# Smarttree_CMU_4.net
KiCad netlist of a schematic drawn in EAGLE
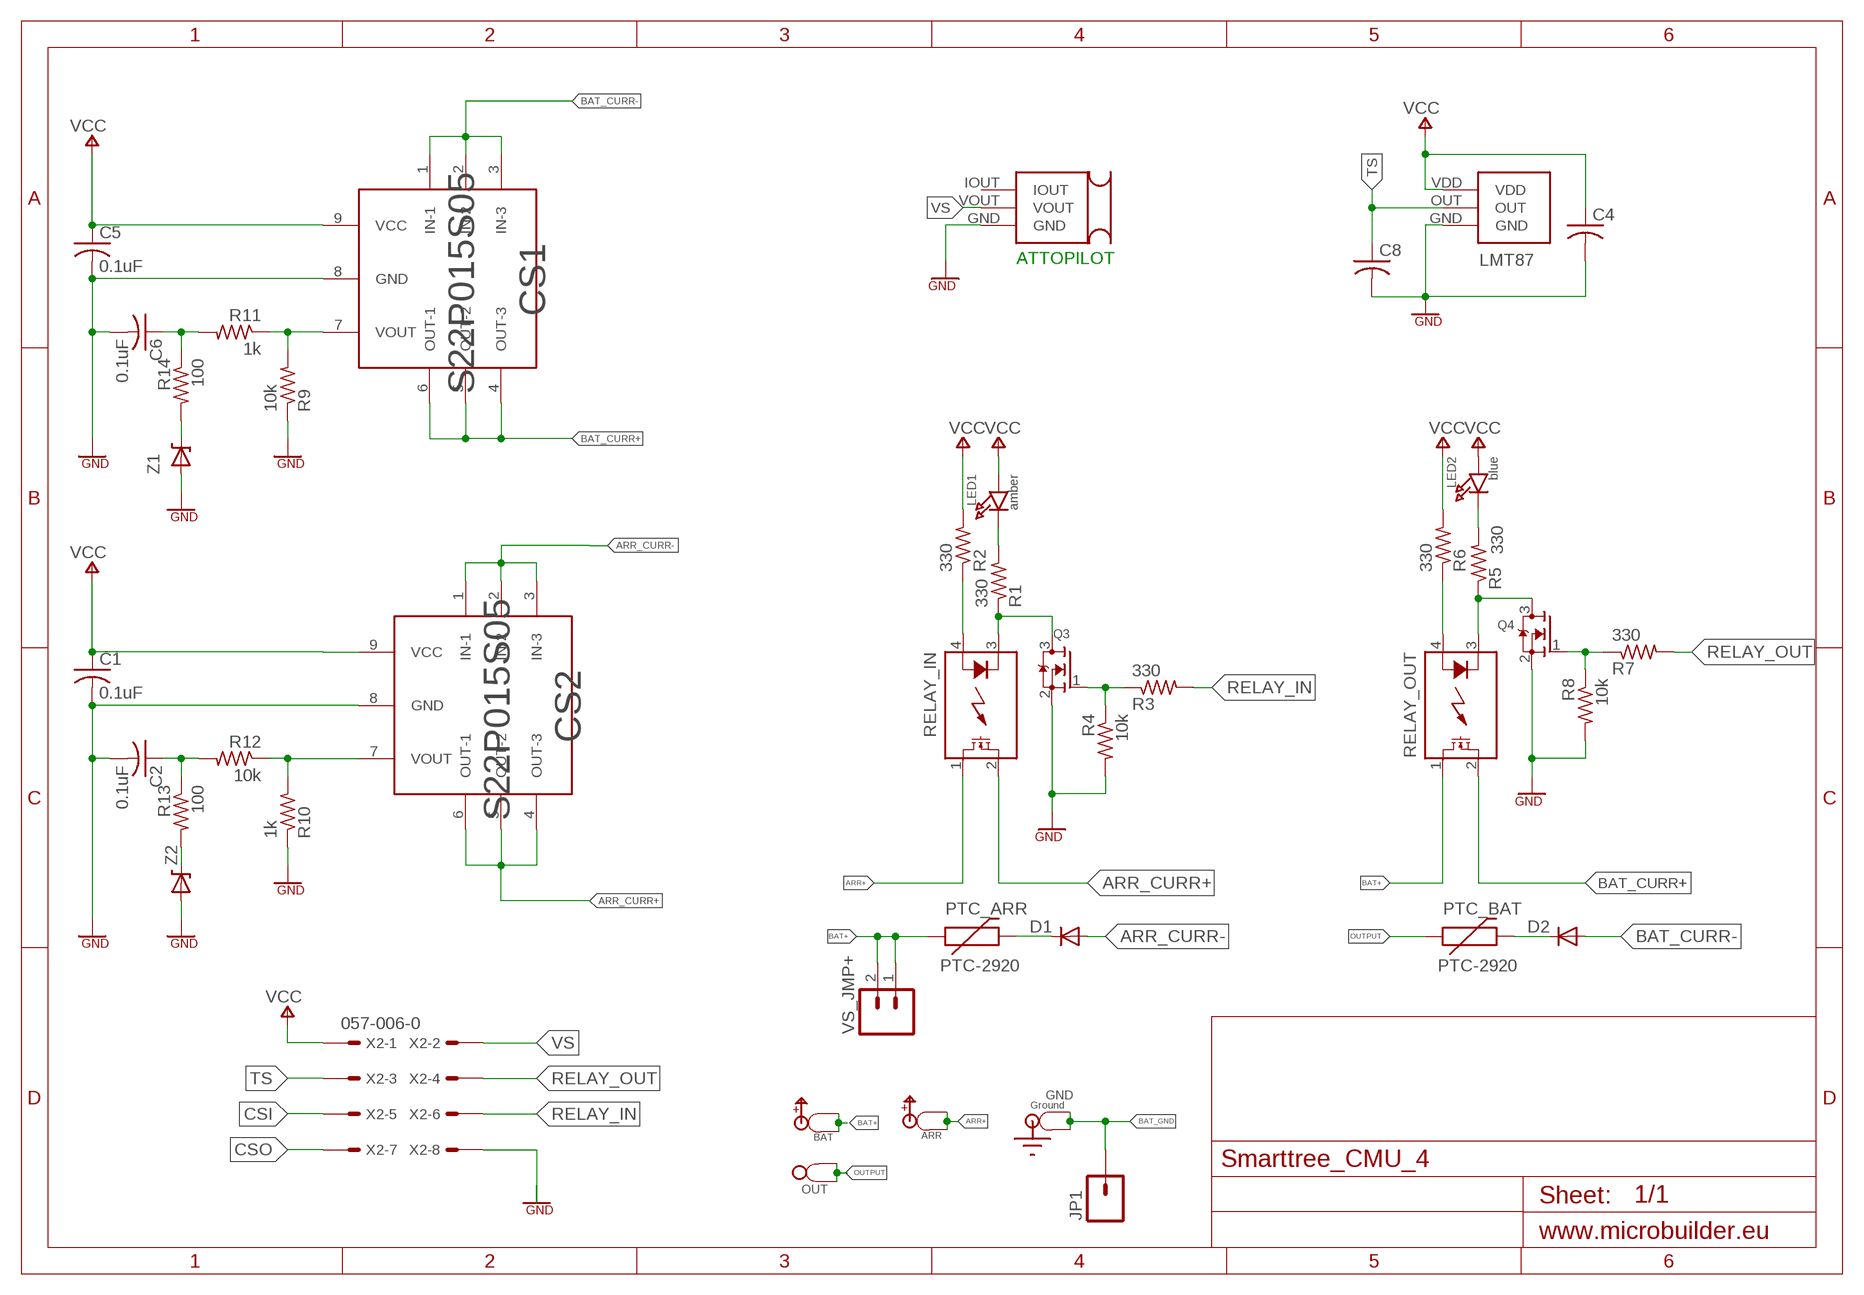
[diagram p0: schematic, sheet 1]

(export (version "E")
  (design (tool "Eeschema 10.0.6"))
  (components
    (comp (ref "ARR")
      (value "SPADE-POWER")
      (footprint "eagle-import:SPADE-POWER")
      (libsource (lib "eagle-import") (part "SPADE-POWER"))
    )
    (comp (ref "ATTOPILOT")
      (value "ATTOPILOT_VOLT")
      (footprint "eagle-import:TH_BKOT")
      (libsource (lib "eagle-import") (part "ATTOPILOT_VOLT"))
    )
    (comp (ref "BAT")
      (value "SPADE-POWER")
      (footprint "eagle-import:SPADE-POWER")
      (libsource (lib "eagle-import") (part "SPADE-POWER"))
    )
    (comp (ref "C1")
      (value "0.1uF")
      (footprint "eagle-import:C0805")
      (libsource (lib "eagle-import") (part "C-USC0805"))
    )
    (comp (ref "C2")
      (value "0.1uF")
      (footprint "eagle-import:C0805")
      (libsource (lib "eagle-import") (part "C-USC0805"))
    )
    (comp (ref "C4")
      (value "C-USC0805")
      (footprint "eagle-import:C0805")
      (libsource (lib "eagle-import") (part "C-USC0805"))
    )
    (comp (ref "C5")
      (value "0.1uF")
      (footprint "eagle-import:C0805")
      (libsource (lib "eagle-import") (part "C-USC0805"))
    )
    (comp (ref "C6")
      (value "0.1uF")
      (footprint "eagle-import:C0805")
      (libsource (lib "eagle-import") (part "C-USC0805"))
    )
    (comp (ref "C8")
      (value "C-USC0805")
      (footprint "eagle-import:C0805")
      (libsource (lib "eagle-import") (part "C-USC0805"))
    )
    (comp (ref "CS1")
      (value "S22P015S05")
      (footprint "eagle-import:S22P015S05")
      (libsource (lib "eagle-import") (part "S22P015S05"))
    )
    (comp (ref "CS2")
      (value "S22P015S05")
      (footprint "eagle-import:S22P015S05")
      (libsource (lib "eagle-import") (part "S22P015S05"))
    )
    (comp (ref "D1")
      (value "DIODE-SOD106-R")
      (footprint "eagle-import:SOD106-R")
      (libsource (lib "eagle-import") (part "DIODE-SOD106-R"))
    )
    (comp (ref "D2")
      (value "DIODE-SOD106-R")
      (footprint "eagle-import:SOD106-R")
      (libsource (lib "eagle-import") (part "DIODE-SOD106-R"))
    )
    (comp (ref "GND")
      (value "SPADE-GROUND")
      (footprint "eagle-import:SPADE-GROUND")
      (libsource (lib "eagle-import") (part "SPADE-GROUND"))
    )
    (comp (ref "JP1")
      (value "M01OFFSET")
      (footprint "eagle-import:1X01_OFFSET")
      (libsource (lib "eagle-import") (part "M01OFFSET"))
    )
    (comp (ref "LED1")
      (value "amber")
      (footprint "eagle-import:CHIPLED_0805")
      (libsource (lib "eagle-import") (part "LED0805"))
    )
    (comp (ref "LED2")
      (value "blue")
      (footprint "eagle-import:CHIPLED_0805")
      (libsource (lib "eagle-import") (part "LED0805"))
    )
    (comp (ref "LMT87")
      (value "LMT87_PAC")
      (footprint "eagle-import:LMT87_TO")
      (libsource (lib "eagle-import") (part "LMT87_PAC"))
    )
    (comp (ref "OUT")
      (value "SPADE-TERMINALPTH")
      (footprint "eagle-import:SPADE-TERMINAL")
      (libsource (lib "eagle-import") (part "SPADE-TERMINALPTH"))
    )
    (comp (ref "PTC_ARR")
      (value "PTC-2920")
      (footprint "eagle-import:PTC-2920")
      (libsource (lib "eagle-import") (part "PTC-2920"))
    )
    (comp (ref "PTC_BAT")
      (value "PTC-2920")
      (footprint "eagle-import:PTC-2920")
      (libsource (lib "eagle-import") (part "PTC-2920"))
    )
    (comp (ref "Q3")
      (value "MOSFET-NREFLOW")
      (footprint "eagle-import:SOT23")
      (libsource (lib "eagle-import") (part "MOSFET-NREFLOW"))
    )
    (comp (ref "Q4")
      (value "MOSFET-NREFLOW")
      (footprint "eagle-import:SOT23")
      (libsource (lib "eagle-import") (part "MOSFET-NREFLOW"))
    )
    (comp (ref "R1")
      (value "330")
      (footprint "eagle-import:R0805")
      (libsource (lib "eagle-import") (part "R-US_R0805"))
    )
    (comp (ref "R2")
      (value "330")
      (footprint "eagle-import:R0805")
      (libsource (lib "eagle-import") (part "R-US_R0805"))
    )
    (comp (ref "R3")
      (value "330")
      (footprint "eagle-import:R0805")
      (libsource (lib "eagle-import") (part "R-US_R0805"))
    )
    (comp (ref "R4")
      (value "10k")
      (footprint "eagle-import:R0805")
      (libsource (lib "eagle-import") (part "R-US_R0805"))
    )
    (comp (ref "R5")
      (value "330")
      (footprint "eagle-import:R0805")
      (libsource (lib "eagle-import") (part "R-US_R0805"))
    )
    (comp (ref "R6")
      (value "330")
      (footprint "eagle-import:R0805")
      (libsource (lib "eagle-import") (part "R-US_R0805"))
    )
    (comp (ref "R7")
      (value "330")
      (footprint "eagle-import:R0805")
      (libsource (lib "eagle-import") (part "R-US_R0805"))
    )
    (comp (ref "R8")
      (value "10k")
      (footprint "eagle-import:R0805")
      (libsource (lib "eagle-import") (part "R-US_R0805"))
    )
    (comp (ref "R9")
      (value "10k")
      (footprint "eagle-import:R0805")
      (libsource (lib "eagle-import") (part "R-US_R0805"))
    )
    (comp (ref "R10")
      (value "1k")
      (footprint "eagle-import:R0805")
      (libsource (lib "eagle-import") (part "R-US_R0805"))
    )
    (comp (ref "R11")
      (value "1k")
      (footprint "eagle-import:R0805")
      (libsource (lib "eagle-import") (part "R-US_R0805"))
    )
    (comp (ref "R12")
      (value "10k")
      (footprint "eagle-import:R0805")
      (libsource (lib "eagle-import") (part "R-US_R0805"))
    )
    (comp (ref "R13")
      (value "100")
      (footprint "eagle-import:R0805")
      (libsource (lib "eagle-import") (part "R-US_R0805"))
    )
    (comp (ref "R14")
      (value "100")
      (footprint "eagle-import:R0805")
      (libsource (lib "eagle-import") (part "R-US_R0805"))
    )
    (comp (ref "RELAY_IN")
      (value "CPC1708J")
      (footprint "eagle-import:I4-PAC")
      (libsource (lib "eagle-import") (part "CPC1708J"))
    )
    (comp (ref "RELAY_OUT")
      (value "CPC1708J")
      (footprint "eagle-import:I4-PAC")
      (libsource (lib "eagle-import") (part "CPC1708J"))
    )
    (comp (ref "VS_JMP+")
      (value "M02")
      (footprint "eagle-import:1X02_LONGPADS")
      (libsource (lib "eagle-import") (part "M02"))
    )
    (comp (ref "X2")
      (value "057-006-0")
      (footprint "eagle-import:057-006-0")
      (libsource (lib "eagle-import") (part "057-006-0"))
    )
    (comp (ref "Z1")
      (value "DIODE-ZENER-BZT52")
      (footprint "eagle-import:SOD-323")
      (libsource (lib "eagle-import") (part "DIODE-ZENER-BZT52"))
    )
    (comp (ref "Z2")
      (value "DIODE-ZENER-BZT52")
      (footprint "eagle-import:SOD-323")
      (libsource (lib "eagle-import") (part "DIODE-ZENER-BZT52"))
    )
  )
  (nets
    (net (code "1") (name "5V") (class "Default")
      (node (ref "C1") (pin "1") (pinfunction "1_1") (pintype "passive"))
      (node (ref "C4") (pin "1") (pinfunction "1_1") (pintype "passive"))
      (node (ref "C5") (pin "1") (pinfunction "1_1") (pintype "passive"))
      (node (ref "CS1") (pin "9") (pinfunction "VCC_9") (pintype "bidirectional"))
      (node (ref "CS2") (pin "9") (pinfunction "VCC_9") (pintype "bidirectional"))
      (node (ref "LED1") (pin "A") (pinfunction "A_A") (pintype "passive"))
      (node (ref "LED2") (pin "A") (pinfunction "A_A") (pintype "passive"))
      (node (ref "LMT87") (pin "VDD") (pinfunction "VDD_VDD") (pintype "bidirectional"))
      (node (ref "R2") (pin "2") (pinfunction "2_2") (pintype "passive"))
      (node (ref "R6") (pin "2") (pinfunction "2_2") (pintype "passive"))
      (node (ref "X2") (pin "1") (pinfunction "S_1") (pintype "passive"))
    )
    (net (code "2") (name "ARR+") (class "Default")
      (node (ref "ARR") (pin "P$1") (pinfunction "P$1_P$1") (pintype "bidirectional"))
      (node (ref "ARR") (pin "P$2") (pinfunction "P$2_P$2") (pintype "bidirectional"))
      (node (ref "RELAY_IN") (pin "1") (pinfunction "DS1_1") (pintype "passive"))
    )
    (net (code "3") (name "ARR_CURR+") (class "Default")
      (node (ref "CS2") (pin "4") (pinfunction "OUT-3_4") (pintype "bidirectional"))
      (node (ref "CS2") (pin "5") (pinfunction "OUT-2_5") (pintype "bidirectional"))
      (node (ref "CS2") (pin "6") (pinfunction "OUT-1_6") (pintype "bidirectional"))
      (node (ref "RELAY_IN") (pin "2") (pinfunction "DS2_2") (pintype "passive"))
    )
    (net (code "4") (name "ARR_CURR-") (class "Default")
      (node (ref "CS2") (pin "1") (pinfunction "IN-1_1") (pintype "bidirectional"))
      (node (ref "CS2") (pin "2") (pinfunction "IN-2_2") (pintype "bidirectional"))
      (node (ref "CS2") (pin "3") (pinfunction "IN-3_3") (pintype "bidirectional"))
      (node (ref "D1") (pin "A") (pinfunction "A_A") (pintype "passive"))
    )
    (net (code "5") (name "BAT+") (class "Default")
      (node (ref "BAT") (pin "P$1") (pinfunction "P$1_P$1") (pintype "bidirectional"))
      (node (ref "BAT") (pin "P$2") (pinfunction "P$2_P$2") (pintype "bidirectional"))
      (node (ref "PTC_ARR") (pin "1") (pinfunction "1_1") (pintype "bidirectional"))
      (node (ref "RELAY_OUT") (pin "1") (pinfunction "DS1_1") (pintype "passive"))
      (node (ref "VS_JMP+") (pin "1") (pinfunction "1_1") (pintype "passive"))
      (node (ref "VS_JMP+") (pin "2") (pinfunction "2_2") (pintype "passive"))
    )
    (net (code "6") (name "BAT_CURR+") (class "Default")
      (node (ref "CS1") (pin "4") (pinfunction "OUT-3_4") (pintype "bidirectional"))
      (node (ref "CS1") (pin "5") (pinfunction "OUT-2_5") (pintype "bidirectional"))
      (node (ref "CS1") (pin "6") (pinfunction "OUT-1_6") (pintype "bidirectional"))
      (node (ref "RELAY_OUT") (pin "2") (pinfunction "DS2_2") (pintype "passive"))
    )
    (net (code "7") (name "BAT_CURR-") (class "Default")
      (node (ref "CS1") (pin "1") (pinfunction "IN-1_1") (pintype "bidirectional"))
      (node (ref "CS1") (pin "2") (pinfunction "IN-2_2") (pintype "bidirectional"))
      (node (ref "CS1") (pin "3") (pinfunction "IN-3_3") (pintype "bidirectional"))
      (node (ref "D2") (pin "A") (pinfunction "A_A") (pintype "passive"))
    )
    (net (code "8") (name "BAT_GND") (class "Default")
      (node (ref "GND") (pin "P$1") (pinfunction "P$1_P$1") (pintype "bidirectional"))
      (node (ref "GND") (pin "P$2") (pinfunction "P$2_P$2") (pintype "bidirectional"))
      (node (ref "JP1") (pin "1") (pinfunction "1_1") (pintype "passive"))
    )
    (net (code "9") (name "CSI") (class "Default")
      (node (ref "C2") (pin "1") (pinfunction "1_1") (pintype "passive"))
      (node (ref "R12") (pin "2") (pinfunction "2_2") (pintype "passive"))
      (node (ref "R13") (pin "1") (pinfunction "1_1") (pintype "passive"))
      (node (ref "X2") (pin "5") (pinfunction "S_5") (pintype "passive"))
    )
    (net (code "10") (name "CSO") (class "Default")
      (node (ref "C6") (pin "1") (pinfunction "1_1") (pintype "passive"))
      (node (ref "R11") (pin "2") (pinfunction "2_2") (pintype "passive"))
      (node (ref "R14") (pin "1") (pinfunction "1_1") (pintype "passive"))
      (node (ref "X2") (pin "8") (pinfunction "S_8") (pintype "passive"))
    )
    (net (code "11") (name "GND") (class "Default")
      (node (ref "ATTOPILOT") (pin "GND") (pinfunction "GND_GND") (pintype "bidirectional"))
      (node (ref "C1") (pin "2") (pinfunction "2_2") (pintype "passive"))
      (node (ref "C2") (pin "2") (pinfunction "2_2") (pintype "passive"))
      (node (ref "C4") (pin "2") (pinfunction "2_2") (pintype "passive"))
      (node (ref "C5") (pin "2") (pinfunction "2_2") (pintype "passive"))
      (node (ref "C6") (pin "2") (pinfunction "2_2") (pintype "passive"))
      (node (ref "C8") (pin "2") (pinfunction "2_2") (pintype "passive"))
      (node (ref "CS1") (pin "8") (pinfunction "GND_8") (pintype "bidirectional"))
      (node (ref "CS2") (pin "8") (pinfunction "GND_8") (pintype "bidirectional"))
      (node (ref "LMT87") (pin "GND") (pinfunction "GND_GND") (pintype "bidirectional"))
      (node (ref "Q3") (pin "2") (pinfunction "S_2") (pintype "bidirectional"))
      (node (ref "Q4") (pin "2") (pinfunction "S_2") (pintype "bidirectional"))
      (node (ref "R10") (pin "1") (pinfunction "1_1") (pintype "passive"))
      (node (ref "R4") (pin "2") (pinfunction "2_2") (pintype "passive"))
      (node (ref "R8") (pin "2") (pinfunction "2_2") (pintype "passive"))
      (node (ref "R9") (pin "1") (pinfunction "1_1") (pintype "passive"))
      (node (ref "X2") (pin "7") (pinfunction "S_7") (pintype "passive"))
      (node (ref "Z1") (pin "2") (pinfunction "A_2") (pintype "passive"))
      (node (ref "Z2") (pin "2") (pinfunction "A_2") (pintype "passive"))
    )
    (net (code "12") (name "Net-(CS1-VOUT)") (class "Default")
      (node (ref "CS1") (pin "7") (pinfunction "VOUT_7") (pintype "bidirectional"))
      (node (ref "R11") (pin "1") (pinfunction "1_1") (pintype "passive"))
      (node (ref "R9") (pin "2") (pinfunction "2_2") (pintype "passive"))
    )
    (net (code "13") (name "Net-(CS2-VOUT)") (class "Default")
      (node (ref "CS2") (pin "7") (pinfunction "VOUT_7") (pintype "bidirectional"))
      (node (ref "R10") (pin "2") (pinfunction "2_2") (pintype "passive"))
      (node (ref "R12") (pin "1") (pinfunction "1_1") (pintype "passive"))
    )
    (net (code "14") (name "Net-(D1-PadC)") (class "Default")
      (node (ref "D1") (pin "C") (pinfunction "C_C") (pintype "passive"))
      (node (ref "PTC_ARR") (pin "2") (pinfunction "2_2") (pintype "bidirectional"))
    )
    (net (code "15") (name "Net-(D2-PadC)") (class "Default")
      (node (ref "D2") (pin "C") (pinfunction "C_C") (pintype "passive"))
      (node (ref "PTC_BAT") (pin "2") (pinfunction "2_2") (pintype "bidirectional"))
    )
    (net (code "16") (name "Net-(LED1-PadC)") (class "Default")
      (node (ref "LED1") (pin "C") (pinfunction "C_C") (pintype "passive"))
      (node (ref "R1") (pin "2") (pinfunction "2_2") (pintype "passive"))
    )
    (net (code "17") (name "Net-(LED2-PadC)") (class "Default")
      (node (ref "LED2") (pin "C") (pinfunction "C_C") (pintype "passive"))
      (node (ref "R5") (pin "2") (pinfunction "2_2") (pintype "passive"))
    )
    (net (code "18") (name "Net-(Q3-D)") (class "Default")
      (node (ref "Q3") (pin "3") (pinfunction "D_3") (pintype "bidirectional"))
      (node (ref "R1") (pin "1") (pinfunction "1_1") (pintype "passive"))
      (node (ref "RELAY_IN") (pin "3") (pinfunction "K_3") (pintype "passive"))
    )
    (net (code "19") (name "Net-(Q3-G)") (class "Default")
      (node (ref "Q3") (pin "1") (pinfunction "G_1") (pintype "bidirectional"))
      (node (ref "R3") (pin "1") (pinfunction "1_1") (pintype "passive"))
      (node (ref "R4") (pin "1") (pinfunction "1_1") (pintype "passive"))
    )
    (net (code "20") (name "Net-(Q4-D)") (class "Default")
      (node (ref "Q4") (pin "3") (pinfunction "D_3") (pintype "bidirectional"))
      (node (ref "R5") (pin "1") (pinfunction "1_1") (pintype "passive"))
      (node (ref "RELAY_OUT") (pin "3") (pinfunction "K_3") (pintype "passive"))
    )
    (net (code "21") (name "Net-(Q4-G)") (class "Default")
      (node (ref "Q4") (pin "1") (pinfunction "G_1") (pintype "bidirectional"))
      (node (ref "R7") (pin "1") (pinfunction "1_1") (pintype "passive"))
      (node (ref "R8") (pin "1") (pinfunction "1_1") (pintype "passive"))
    )
    (net (code "22") (name "Net-(RELAY_IN-A)") (class "Default")
      (node (ref "R2") (pin "1") (pinfunction "1_1") (pintype "passive"))
      (node (ref "RELAY_IN") (pin "4") (pinfunction "A_4") (pintype "passive"))
    )
    (net (code "23") (name "Net-(RELAY_OUT-A)") (class "Default")
      (node (ref "R6") (pin "1") (pinfunction "1_1") (pintype "passive"))
      (node (ref "RELAY_OUT") (pin "4") (pinfunction "A_4") (pintype "passive"))
    )
    (net (code "24") (name "Net-(Z1-C)") (class "Default")
      (node (ref "R14") (pin "2") (pinfunction "2_2") (pintype "passive"))
      (node (ref "Z1") (pin "1") (pinfunction "C_1") (pintype "passive"))
    )
    (net (code "25") (name "Net-(Z2-C)") (class "Default")
      (node (ref "R13") (pin "2") (pinfunction "2_2") (pintype "passive"))
      (node (ref "Z2") (pin "1") (pinfunction "C_1") (pintype "passive"))
    )
    (net (code "26") (name "OUTPUT") (class "Default")
      (node (ref "OUT") (pin "P$1") (pinfunction "P$1_P$1") (pintype "bidirectional"))
      (node (ref "OUT") (pin "P$2") (pinfunction "P$2_P$2") (pintype "bidirectional"))
      (node (ref "PTC_BAT") (pin "1") (pinfunction "1_1") (pintype "bidirectional"))
    )
    (net (code "27") (name "RELAY_IN") (class "Default")
      (node (ref "R3") (pin "2") (pinfunction "2_2") (pintype "passive"))
      (node (ref "X2") (pin "6") (pinfunction "S_6") (pintype "passive"))
    )
    (net (code "28") (name "RELAY_OUT") (class "Default")
      (node (ref "R7") (pin "2") (pinfunction "2_2") (pintype "passive"))
      (node (ref "X2") (pin "4") (pinfunction "S_4") (pintype "passive"))
    )
    (net (code "29") (name "TS") (class "Default")
      (node (ref "C8") (pin "1") (pinfunction "1_1") (pintype "passive"))
      (node (ref "LMT87") (pin "OUT") (pinfunction "OUT_OUT") (pintype "bidirectional"))
      (node (ref "X2") (pin "3") (pinfunction "S_3") (pintype "passive"))
    )
    (net (code "30") (name "VS") (class "Default")
      (node (ref "ATTOPILOT") (pin "VOUT") (pinfunction "VOUT_VOUT") (pintype "bidirectional"))
      (node (ref "X2") (pin "2") (pinfunction "S_2") (pintype "passive"))
    )
    (net (code "31") (name "unconnected-(ATTOPILOT-PadIOUT)") (class "Default")
      (node (ref "ATTOPILOT") (pin "IOUT") (pinfunction "IOUT_IOUT") (pintype "bidirectional"))
    )
  )
)
